# Sch_bai7.net
KiCad netlist of a schematic drawn in Altium Designer
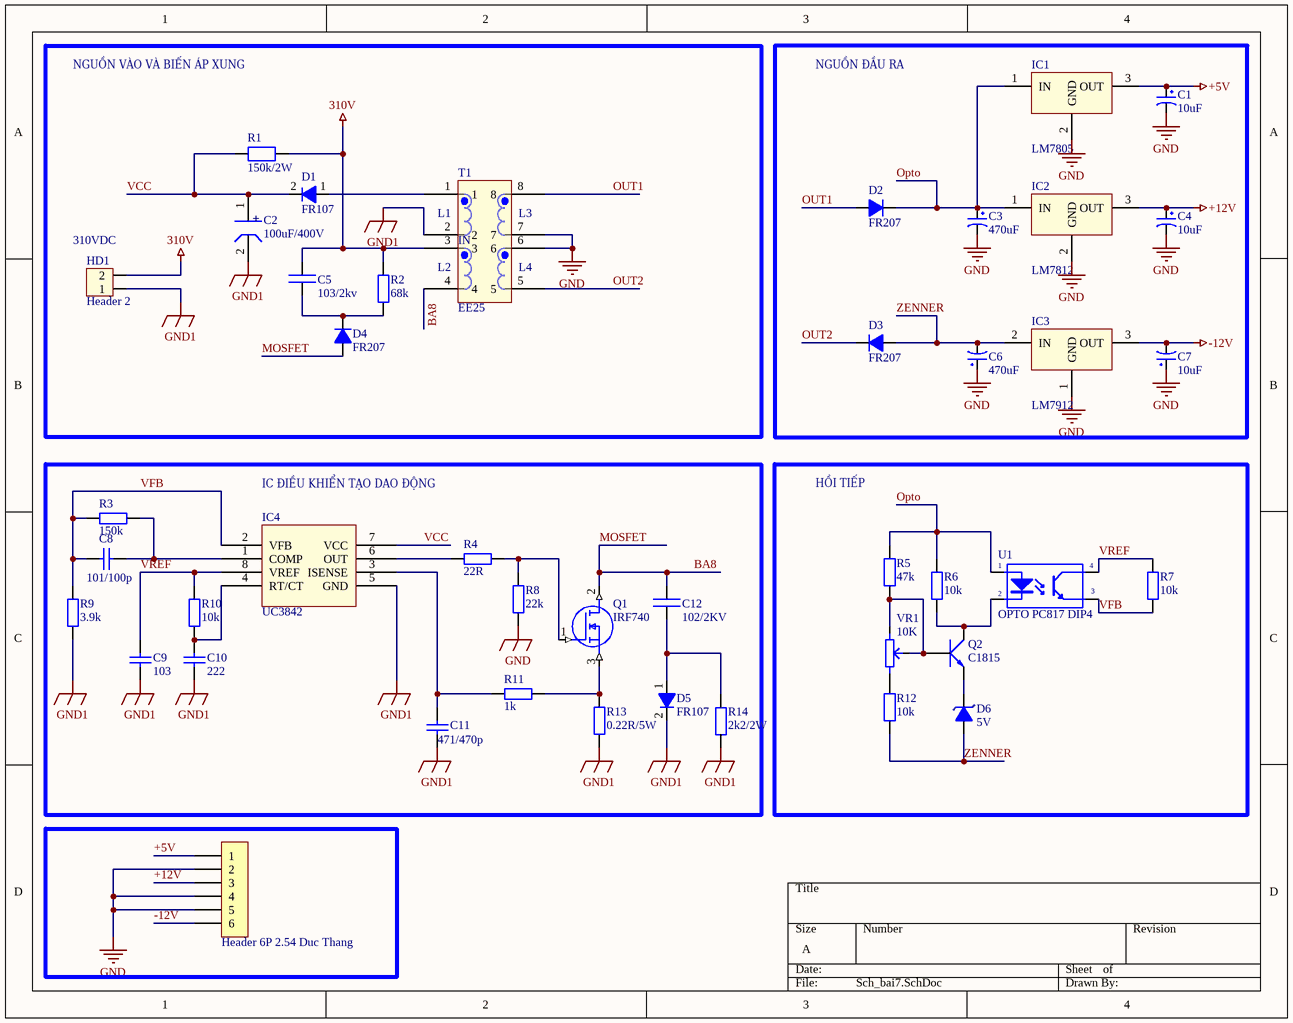
[diagram p0: Sch_bai7.SchDoc]

(export (version "E")
  (design (tool "Eeschema 10.0.6"))
  (components
    (comp (ref "C1")
      (value "10uF")
      (footprint "tu hoa 4mm")
      (description "Cắm")
      (libsource (lib "Tu dien") (part "Tu Hoa 10uF 25V 4x7"))
    )
    (comp (ref "C2")
      (value "100uF/400V")
      (footprint "Cap_100uF/400V")
      (libsource (lib "test") (part "cap_100uF/400V"))
    )
    (comp (ref "C3")
      (value "470uF")
      (footprint "tu hoa 10mm")
      (description "Cắm")
      (libsource (lib "Tu dien") (part "Tu Hoa 470uF 50V 10x17"))
    )
    (comp (ref "C4")
      (value "10uF")
      (footprint "tu hoa 4mm")
      (description "Cắm")
      (libsource (lib "Tu dien") (part "Tu Hoa 10uF 25V 4x7"))
    )
    (comp (ref "C5")
      (value "103/2kv")
      (footprint "Cap_103/2kv")
      (libsource (lib "test") (part "cap_103/2kv"))
    )
    (comp (ref "C6")
      (value "470uF")
      (footprint "tu hoa 10mm")
      (description "Cắm")
      (libsource (lib "Tu dien") (part "Tu Hoa 470uF 50V 10x17"))
    )
    (comp (ref "C7")
      (value "10uF")
      (footprint "tu hoa 4mm")
      (description "Cắm")
      (libsource (lib "Tu dien") (part "Tu Hoa 10uF 25V 4x7"))
    )
    (comp (ref "C8")
      (value "101/100p")
      (footprint "tu gom")
      (description "Cắm")
      (libsource (lib "Tu dien") (part "Tu gom 101 50V"))
    )
    (comp (ref "C9")
      (value "103")
      (footprint "tu gom")
      (description "Cắm")
      (libsource (lib "Tu dien") (part "Tu gom 103 50V"))
    )
    (comp (ref "C10")
      (value "222")
      (footprint "tu gom")
      (description "Cắm")
      (libsource (lib "Tu dien") (part "Tu gom 222 50V"))
    )
    (comp (ref "C11")
      (value "471/470p")
      (footprint "tu gom")
      (description "Cắm")
      (libsource (lib "Tu dien") (part "Tu gom 471 50V"))
    )
    (comp (ref "C12")
      (value "102/2KV")
      (footprint "Cap_102_2KV")
      (description "Tụ cao áp")
      (libsource (lib "test") (part "Cap_102/2KV"))
    )
    (comp (ref "D1") (value "FR107") (footprint "Diode_FR107") (libsource (lib "test") (part "Diode_FR107")))
    (comp (ref "D2")
      (value "FR207")
      (footprint "DIODE 2A")
      (description "Cắm")
      (libsource (lib "Diode") (part "Diode FR207"))
    )
    (comp (ref "D3")
      (value "FR207")
      (footprint "DIODE 2A")
      (description "Cắm")
      (libsource (lib "Diode") (part "Diode FR207"))
    )
    (comp (ref "D4")
      (value "FR207")
      (footprint "DIODE 2A")
      (description "Cắm")
      (libsource (lib "Diode") (part "Diode FR207"))
    )
    (comp (ref "D5") (value "FR107") (footprint "Diode_FR107") (libsource (lib "test") (part "Diode_FR107")))
    (comp (ref "D6") (value "5V") (footprint "D1A") (libsource (lib "syhaunguyen") (part "Zener")))
    (comp (ref "H1")
      (value "Header 6P 2.54 Duc Thang")
      (footprint "XH2.54M-6")
      (description "Cắm")
      (libsource (lib "Header") (part "Header 6P 2.54 Duc Thang"))
    )
    (comp (ref "HD1")
      (value "Header 2")
      (footprint "HED2")
      (description "Header 2 (Green)")
      (libsource (lib "syhaunguyen") (part "Hed2"))
    )
    (comp (ref "IC1")
      (value "LM7805")
      (footprint "QTO-220")
      (description "On ap +, from + 5 to + 24VDC")
      (libsource (lib "syhaunguyen") (part "LM78xx"))
    )
    (comp (ref "IC2") (value "LM7812") (footprint "LM7812") (libsource (lib "test") (part "LM7812")))
    (comp (ref "IC3") (value "LM7912") (footprint "LM7912") (libsource (lib "test") (part "LM7912")))
    (comp (ref "IC4") (value "UC3842") (footprint "UC3842_DIP") (libsource (lib "test") (part "UC3842")))
    (comp (ref "Q1") (value "IRF740") (footprint "IRF740") (libsource (lib "test") (part "IRF740")))
    (comp (ref "Q2")
      (value "C1815")
      (footprint "TO92")
      (description "NPN transistor")
      (libsource (lib "TranFet") (part "C1815"))
    )
    (comp (ref "R1")
      (value "150k/2W")
      (footprint "Tro Vach 2W")
      (libsource (lib "test") (part "Res_150k/2W"))
    )
    (comp (ref "R2")
      (value "68k")
      (footprint "tro vach 1/4w")
      (description "Cắm")
      (libsource (lib "Dien Tro") (part "Tro Vach 1/4W 5% 68k"))
    )
    (comp (ref "R3")
      (value "150k")
      (footprint "Tro vach 1/4w")
      (description "Cắm")
      (libsource (lib "Dien Tro") (part "Tro Vach 1/4W 5% 150k"))
    )
    (comp (ref "R4")
      (value "22R")
      (footprint "tro vach 1/4w")
      (description "Cắm")
      (libsource (lib "Dien Tro") (part "Tro Vach 1/4W 5% 22R"))
    )
    (comp (ref "R5")
      (value "47k")
      (footprint "tro vach 1/4w")
      (description "Cắm")
      (libsource (lib "Dien Tro") (part "Tro Vach 1/4W 5% 47k"))
    )
    (comp (ref "R6")
      (value "10k")
      (footprint "tro vach 1/4w")
      (description "Căm")
      (libsource (lib "Dien Tro") (part "Tro Vach 1/4W 5% 10k"))
    )
    (comp (ref "R7")
      (value "10k")
      (footprint "tro vach 1/4w")
      (description "Căm")
      (libsource (lib "Dien Tro") (part "Tro Vach 1/4W 5% 10k"))
    )
    (comp (ref "R8")
      (value "22k")
      (footprint "tro vach 1/4w")
      (description "Cắm")
      (libsource (lib "Dien Tro") (part "Tro Vach 1/4W 5% 22k"))
    )
    (comp (ref "R9")
      (value "3.9k")
      (footprint "tro vach 1/4w")
      (description "Cắm")
      (libsource (lib "Dien Tro") (part "Tro Vach 1/4W 5% 3.9k"))
    )
    (comp (ref "R10")
      (value "10k")
      (footprint "tro vach 1/4w")
      (description "Căm")
      (libsource (lib "Dien Tro") (part "Tro Vach 1/4W 5% 10k"))
    )
    (comp (ref "R11")
      (value "1k")
      (footprint "tro vach 1/4w")
      (description "Cắm")
      (libsource (lib "Dien Tro") (part "Tro Vach 1/4W 5% 1k"))
    )
    (comp (ref "R12")
      (value "10k")
      (footprint "tro vach 1/4w")
      (description "Căm")
      (libsource (lib "Dien Tro") (part "Tro Vach 1/4W 5% 10k"))
    )
    (comp (ref "R13")
      (value "0.22R/5W")
      (footprint "tro cong suat 5w")
      (description "Cắm")
      (libsource (lib "Dien Tro") (part "Tro Cong Suat 5W 5% 0.22R"))
    )
    (comp (ref "R14") (value "2k2/2W") (footprint "Tro Vach 2W") (libsource (lib "test") (part "res-2k2/2W")))
    (comp (ref "T1")
      (value "EE25")
      (footprint "EE25_8_PIN")
      (libsource (lib "test") (part "Transformer EE25_8pin"))
    )
    (comp (ref "U1")
      (value "OPTO PC817 DIP4")
      (footprint "DIP4")
      (description "Single Opto")
      (libsource (lib "IC") (part "OPTO PC817 DIP4"))
    )
    (comp (ref "VR1")
      (value "10K")
      (footprint "Bien Tro Tam Giac Dung")
      (description "Cắm")
      (libsource (lib "Dien Tro") (part "Bien tro tam giac 10K Dung"))
    )
  )
  (nets
    (net (code "1") (name "+5V") (class "Default")
      (node (ref "C1") (pin "1") (pinfunction "1_1") (pintype "passive"))
      (node (ref "H1") (pin "1") (pinfunction "1_1") (pintype "passive"))
      (node (ref "IC1") (pin "3") (pinfunction "OUT_3") (pintype "passive"))
    )
    (net (code "2") (name "+12V") (class "Default")
      (node (ref "C4") (pin "1") (pinfunction "1_1") (pintype "passive"))
      (node (ref "H1") (pin "3") (pinfunction "3_3") (pintype "passive"))
      (node (ref "IC2") (pin "3") (pinfunction "OUT_3") (pintype "passive"))
    )
    (net (code "3") (name "-12V") (class "Default")
      (node (ref "C7") (pin "2") (pinfunction "2_2") (pintype "passive"))
      (node (ref "H1") (pin "6") (pinfunction "6_6") (pintype "passive"))
      (node (ref "IC3") (pin "3") (pinfunction "OUT_3") (pintype "passive"))
    )
    (net (code "4") (name "/BA8") (class "Default")
      (node (ref "C12") (pin "2") (pintype "passive"))
      (node (ref "D4") (pin "1") (pinfunction "A_1") (pintype "passive"))
      (node (ref "Q1") (pin "2") (pinfunction "D_2") (pintype "output"))
      (node (ref "T1") (pin "4") (pinfunction "4_4") (pintype "passive"))
    )
    (net (code "5") (name "/OUT1") (class "Default")
      (node (ref "D2") (pin "1") (pinfunction "A_1") (pintype "passive"))
      (node (ref "T1") (pin "8") (pinfunction "8_8") (pintype "passive"))
    )
    (net (code "6") (name "/OUT2") (class "Default")
      (node (ref "D3") (pin "2") (pinfunction "K_2") (pintype "passive"))
      (node (ref "T1") (pin "5") (pinfunction "5_5") (pintype "passive"))
    )
    (net (code "7") (name "/Opto") (class "Default")
      (node (ref "C3") (pin "1") (pinfunction "1_1") (pintype "passive"))
      (node (ref "D2") (pin "2") (pinfunction "K_2") (pintype "passive"))
      (node (ref "IC1") (pin "1") (pinfunction "IN_1") (pintype "passive"))
      (node (ref "IC2") (pin "1") (pinfunction "IN_1") (pintype "passive"))
      (node (ref "R5") (pin "2") (pinfunction "2_2") (pintype "passive"))
      (node (ref "R6") (pin "1") (pinfunction "1_1") (pintype "passive"))
      (node (ref "U1") (pin "1") (pinfunction "A_1") (pintype "passive"))
    )
    (net (code "8") (name "/VCC") (class "Default")
      (node (ref "C2") (pin "1") (pintype "passive"))
      (node (ref "D1") (pin "2") (pintype "passive"))
      (node (ref "IC4") (pin "7") (pinfunction "VCC_7") (pintype "passive"))
      (node (ref "R1") (pin "1") (pintype "passive"))
    )
    (net (code "9") (name "/VFB") (class "Default")
      (node (ref "C8") (pin "1") (pinfunction "1_1") (pintype "passive"))
      (node (ref "IC4") (pin "2") (pinfunction "VFB_2") (pintype "passive"))
      (node (ref "R3") (pin "2") (pinfunction "2_2") (pintype "passive"))
      (node (ref "R7") (pin "2") (pinfunction "2_2") (pintype "passive"))
      (node (ref "R9") (pin "2") (pinfunction "2_2") (pintype "passive"))
      (node (ref "U1") (pin "3") (pinfunction "E_3") (pintype "passive"))
    )
    (net (code "10") (name "/VREF") (class "Default")
      (node (ref "C9") (pin "1") (pinfunction "1_1") (pintype "passive"))
      (node (ref "IC4") (pin "8") (pinfunction "VREF_8") (pintype "passive"))
      (node (ref "R10") (pin "1") (pinfunction "1_1") (pintype "passive"))
      (node (ref "R7") (pin "1") (pinfunction "1_1") (pintype "passive"))
      (node (ref "U1") (pin "4") (pinfunction "C_4") (pintype "passive"))
    )
    (net (code "11") (name "/ZENNER") (class "Default")
      (node (ref "C6") (pin "2") (pinfunction "2_2") (pintype "passive"))
      (node (ref "D3") (pin "1") (pinfunction "A_1") (pintype "passive"))
      (node (ref "D6") (pin "1") (pinfunction "A_1") (pintype "passive"))
      (node (ref "IC3") (pin "2") (pinfunction "IN_2") (pintype "passive"))
      (node (ref "R12") (pin "2") (pinfunction "2_2") (pintype "passive"))
    )
    (net (code "12") (name "310V") (class "Default")
      (node (ref "C5") (pin "2") (pintype "passive"))
      (node (ref "HD1") (pin "2") (pinfunction "2_2") (pintype "passive"))
      (node (ref "R1") (pin "2") (pintype "passive"))
      (node (ref "R2") (pin "2") (pinfunction "2_2") (pintype "passive"))
      (node (ref "T1") (pin "3") (pinfunction "3_3") (pintype "passive"))
    )
    (net (code "13") (name "GND") (class "Default")
      (node (ref "C1") (pin "2") (pinfunction "2_2") (pintype "passive"))
      (node (ref "C3") (pin "2") (pinfunction "2_2") (pintype "passive"))
      (node (ref "C4") (pin "2") (pinfunction "2_2") (pintype "passive"))
      (node (ref "C6") (pin "1") (pinfunction "1_1") (pintype "passive"))
      (node (ref "C7") (pin "1") (pinfunction "1_1") (pintype "passive"))
      (node (ref "H1") (pin "2") (pinfunction "2_2") (pintype "passive"))
      (node (ref "H1") (pin "4") (pinfunction "4_4") (pintype "passive"))
      (node (ref "H1") (pin "5") (pinfunction "5_5") (pintype "passive"))
      (node (ref "IC1") (pin "2") (pinfunction "GND_2") (pintype "passive"))
      (node (ref "IC2") (pin "2") (pinfunction "GND_2") (pintype "passive"))
      (node (ref "IC3") (pin "1") (pinfunction "GND_1") (pintype "passive"))
      (node (ref "R8") (pin "1") (pinfunction "1_1") (pintype "passive"))
      (node (ref "T1") (pin "6") (pinfunction "6_6") (pintype "passive"))
      (node (ref "T1") (pin "7") (pinfunction "7_7") (pintype "passive"))
    )
    (net (code "14") (name "GND1") (class "Default")
      (node (ref "C10") (pin "2") (pinfunction "2_2") (pintype "passive"))
      (node (ref "C11") (pin "2") (pinfunction "2_2") (pintype "passive"))
      (node (ref "C2") (pin "2") (pintype "passive"))
      (node (ref "C9") (pin "2") (pinfunction "2_2") (pintype "passive"))
      (node (ref "D5") (pin "2") (pintype "passive"))
      (node (ref "HD1") (pin "1") (pinfunction "1_1") (pintype "passive"))
      (node (ref "IC4") (pin "5") (pinfunction "GND_5") (pintype "passive"))
      (node (ref "R13") (pin "1") (pinfunction "1_1") (pintype "passive"))
      (node (ref "R14") (pin "1") (pintype "passive"))
      (node (ref "R9") (pin "1") (pinfunction "1_1") (pintype "passive"))
      (node (ref "T1") (pin "2") (pinfunction "2_2") (pintype "passive"))
    )
    (net (code "15") (name "Net-(C12-Pad1)") (class "Default")
      (node (ref "C12") (pin "1") (pintype "passive"))
      (node (ref "D5") (pin "1") (pintype "passive"))
      (node (ref "R14") (pin "2") (pintype "passive"))
    )
    (net (code "16") (name "Net-(D1-Pad1)") (class "Default")
      (node (ref "D1") (pin "1") (pintype "passive"))
      (node (ref "T1") (pin "1") (pinfunction "1_1") (pintype "passive"))
    )
    (net (code "17") (name "Net-(D4-K)") (class "Default")
      (node (ref "C5") (pin "1") (pintype "passive"))
      (node (ref "D4") (pin "2") (pinfunction "K_2") (pintype "passive"))
      (node (ref "R2") (pin "1") (pinfunction "1_1") (pintype "passive"))
    )
    (net (code "18") (name "Net-(D6-K)") (class "Default")
      (node (ref "D6") (pin "2") (pinfunction "K_2") (pintype "passive"))
      (node (ref "Q2") (pin "1") (pinfunction "E_1") (pintype "passive"))
    )
    (net (code "19") (name "Net-(IC4-COMP)") (class "Default")
      (node (ref "C8") (pin "2") (pinfunction "2_2") (pintype "passive"))
      (node (ref "IC4") (pin "1") (pinfunction "COMP_1") (pintype "passive"))
      (node (ref "R3") (pin "1") (pinfunction "1_1") (pintype "passive"))
    )
    (net (code "20") (name "Net-(IC4-ISENSE)") (class "Default")
      (node (ref "C11") (pin "1") (pinfunction "1_1") (pintype "passive"))
      (node (ref "IC4") (pin "3") (pinfunction "ISENSE_3") (pintype "passive"))
      (node (ref "R11") (pin "1") (pinfunction "1_1") (pintype "passive"))
    )
    (net (code "21") (name "Net-(IC4-OUT)") (class "Default")
      (node (ref "IC4") (pin "6") (pinfunction "OUT_6") (pintype "passive"))
      (node (ref "R4") (pin "1") (pinfunction "1_1") (pintype "passive"))
    )
    (net (code "22") (name "Net-(IC4-RT{slash}CT)") (class "Default")
      (node (ref "C10") (pin "1") (pinfunction "1_1") (pintype "passive"))
      (node (ref "IC4") (pin "4") (pinfunction "RT/CT_4") (pintype "passive"))
      (node (ref "R10") (pin "2") (pinfunction "2_2") (pintype "passive"))
    )
    (net (code "23") (name "Net-(Q1-G)") (class "Default")
      (node (ref "Q1") (pin "1") (pinfunction "G_1") (pintype "input"))
      (node (ref "R4") (pin "2") (pinfunction "2_2") (pintype "passive"))
      (node (ref "R8") (pin "2") (pinfunction "2_2") (pintype "passive"))
    )
    (net (code "24") (name "Net-(Q1-S)") (class "Default")
      (node (ref "Q1") (pin "3") (pinfunction "S_3") (pintype "input"))
      (node (ref "R11") (pin "2") (pinfunction "2_2") (pintype "passive"))
      (node (ref "R13") (pin "2") (pinfunction "2_2") (pintype "passive"))
    )
    (net (code "25") (name "Net-(Q2-B)") (class "Default")
      (node (ref "Q2") (pin "3") (pinfunction "B_3") (pintype "passive"))
      (node (ref "R5") (pin "1") (pinfunction "1_1") (pintype "passive"))
      (node (ref "VR1") (pin "1") (pinfunction "1_1") (pintype "passive"))
      (node (ref "VR1") (pin "2") (pinfunction "2_2") (pintype "passive"))
    )
    (net (code "26") (name "Net-(Q2-C)") (class "Default")
      (node (ref "Q2") (pin "2") (pinfunction "C_2") (pintype "passive"))
      (node (ref "R6") (pin "2") (pinfunction "2_2") (pintype "passive"))
      (node (ref "U1") (pin "2") (pinfunction "K_2") (pintype "passive"))
    )
    (net (code "27") (name "Net-(R12-Pad1)") (class "Default")
      (node (ref "R12") (pin "1") (pinfunction "1_1") (pintype "passive"))
      (node (ref "VR1") (pin "3") (pinfunction "3_3") (pintype "passive"))
    )
  )
)
